# 7_power_prot_mon.net
KiCad netlist of a schematic drawn in Altium Designer
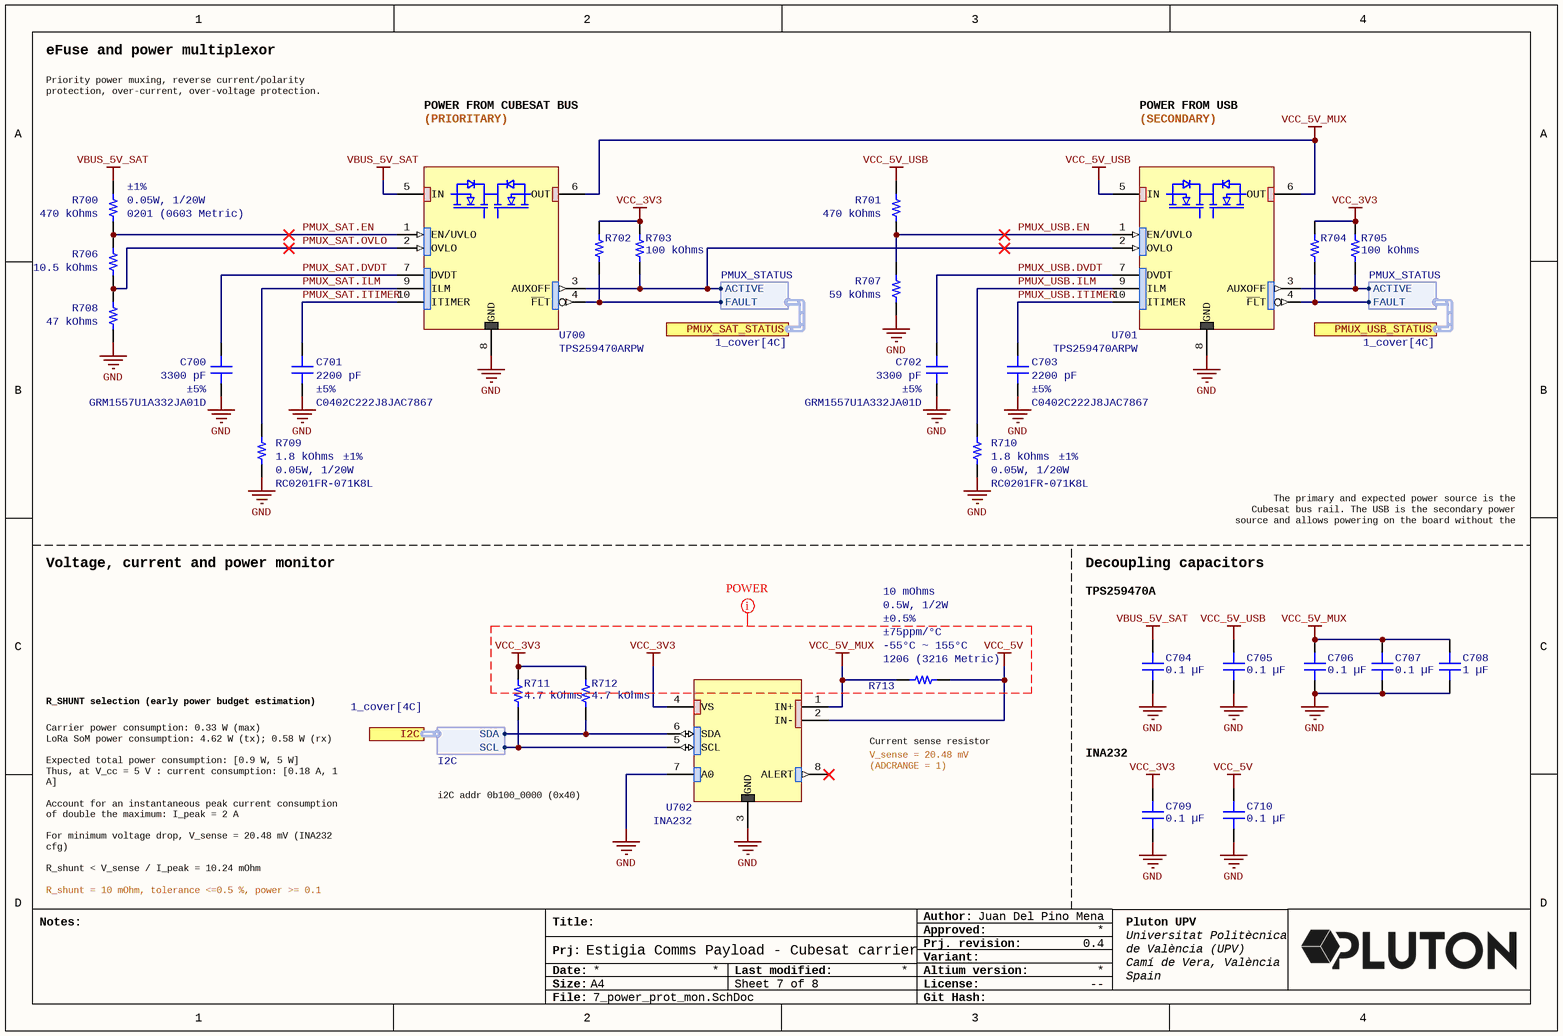
[diagram p0: 7_power_prot_mon.SchDoc]

(export (version "E")
  (design (tool "Eeschema 10.0.6"))
  (components
    (comp (ref "C700")
      (value "3300 pF")
      (footprint "CAP 0402_1005")
      (description "CAP CER 3300PF 10V U2J 0402")
      (fields
        (field (name "PART NUMBER") "GRM1557U1A332JA01D")
        (field (name "MANUFACTURER") "Murata Electronics")
        (field (name "TOLERANCE") "±5%")
      )
      (libsource (lib "Celestial Altium Library - altium_library") (part "Capacitor"))
    )
    (comp (ref "C701")
      (value "2200 pF")
      (footprint "CAP 0402_1005")
      (description "CAP CER 2200PF 10V U2J 0402")
      (fields
        (field (name "PART NUMBER") "C0402C222J8JAC7867")
        (field (name "MANUFACTURER") "KEMET")
        (field (name "TOLERANCE") "±5%")
      )
      (libsource (lib "Celestial Altium Library - altium_library") (part "Capacitor"))
    )
    (comp (ref "C702")
      (value "3300 pF")
      (footprint "CAP 0402_1005")
      (description "CAP CER 3300PF 10V U2J 0402")
      (fields
        (field (name "PART NUMBER") "GRM1557U1A332JA01D")
        (field (name "MANUFACTURER") "Murata Electronics")
        (field (name "TOLERANCE") "±5%")
      )
      (libsource (lib "Celestial Altium Library - altium_library") (part "Capacitor"))
    )
    (comp (ref "C703")
      (value "2200 pF")
      (footprint "CAP 0402_1005")
      (description "CAP CER 2200PF 10V U2J 0402")
      (fields
        (field (name "PART NUMBER") "C0402C222J8JAC7867")
        (field (name "MANUFACTURER") "KEMET")
        (field (name "TOLERANCE") "±5%")
      )
      (libsource (lib "Celestial Altium Library - altium_library") (part "Capacitor"))
    )
    (comp (ref "C704")
      (value "0.1 µF")
      (footprint "CAP 0402_1005")
      (description "CAP CER 0402 0.1UF 16V X7R 10%")
      (fields (field (name "PART NUMBER") "C0402C104K4RECAUTO") (field (name "MANUFACTURER") "KEMET"))
      (libsource (lib "Celestial Altium Library - altium_library") (part "Capacitor"))
    )
    (comp (ref "C705")
      (value "0.1 µF")
      (footprint "CAP 0402_1005")
      (description "CAP CER 0402 0.1UF 16V X7R 10%")
      (fields (field (name "PART NUMBER") "C0402C104K4RECAUTO") (field (name "MANUFACTURER") "KEMET"))
      (libsource (lib "Celestial Altium Library - altium_library") (part "Capacitor"))
    )
    (comp (ref "C706")
      (value "0.1 µF")
      (footprint "CAP 0402_1005")
      (description "CAP CER 0402 0.1UF 16V X7R 10%")
      (fields (field (name "PART NUMBER") "C0402C104K4RECAUTO") (field (name "MANUFACTURER") "KEMET"))
      (libsource (lib "Celestial Altium Library - altium_library") (part "Capacitor"))
    )
    (comp (ref "C707")
      (value "0.1 µF")
      (footprint "CAP 0402_1005")
      (description "CAP CER 0402 0.1UF 16V X7R 10%")
      (fields (field (name "PART NUMBER") "C0402C104K4RECAUTO") (field (name "MANUFACTURER") "KEMET"))
      (libsource (lib "Celestial Altium Library - altium_library") (part "Capacitor"))
    )
    (comp (ref "C708")
      (value "1 µF")
      (footprint "CAP 0402_1005")
      (description "CAP CER 1UF 10V X7S 0402")
      (fields
        (field (name "PART NUMBER") "GRT155C71A105KE13D")
        (field (name "MANUFACTURER") "Murata Electronics")
      )
      (libsource (lib "Celestial Altium Library - altium_library") (part "Capacitor"))
    )
    (comp (ref "C709")
      (value "0.1 µF")
      (footprint "CAP 0402_1005")
      (description "CAP CER 0402 0.1UF 16V X7R 10%")
      (fields (field (name "PART NUMBER") "C0402C104K4RECAUTO") (field (name "MANUFACTURER") "KEMET"))
      (libsource (lib "Celestial Altium Library - altium_library") (part "Capacitor"))
    )
    (comp (ref "C710")
      (value "0.1 µF")
      (footprint "CAP 0402_1005")
      (description "CAP CER 0402 0.1UF 16V X7R 10%")
      (fields (field (name "PART NUMBER") "C0402C104K4RECAUTO") (field (name "MANUFACTURER") "KEMET"))
      (libsource (lib "Celestial Altium Library - altium_library") (part "Capacitor"))
    )
    (comp (ref "R700")
      (value "470 kOhms")
      (footprint "RES 0201_0603")
      (description "RES 470K OHM 1% 1/20W 0201")
      (fields (field (name "PART NUMBER") "RC0201FR-13470KL") (field (name "MANUFACTURER") "Yageo"))
      (libsource (lib "Celestial Altium Library - altium_library") (part "Resistor"))
    )
    (comp (ref "R701")
      (value "470 kOhms")
      (footprint "RES 0201_0603")
      (description "RES 470K OHM 1% 1/20W 0201")
      (fields (field (name "PART NUMBER") "RC0201FR-13470KL") (field (name "MANUFACTURER") "Yageo"))
      (libsource (lib "Celestial Altium Library - altium_library") (part "Resistor"))
    )
    (comp (ref "R702")
      (value "100 kOhms")
      (footprint "RES 0201_0603")
      (description "RES 100K OHM 1% 1/20W 0201")
      (fields (field (name "PART NUMBER") "RC0201FR-13100KL") (field (name "MANUFACTURER") "Yageo"))
      (libsource (lib "Celestial Altium Library - altium_library") (part "Resistor"))
    )
    (comp (ref "R703")
      (value "100 kOhms")
      (footprint "RES 0201_0603")
      (description "RES 100K OHM 1% 1/20W 0201")
      (fields (field (name "PART NUMBER") "RC0201FR-13100KL") (field (name "MANUFACTURER") "Yageo"))
      (libsource (lib "Celestial Altium Library - altium_library") (part "Resistor"))
    )
    (comp (ref "R704")
      (value "100 kOhms")
      (footprint "RES 0201_0603")
      (description "RES 100K OHM 1% 1/20W 0201")
      (fields (field (name "PART NUMBER") "RC0201FR-13100KL") (field (name "MANUFACTURER") "Yageo"))
      (libsource (lib "Celestial Altium Library - altium_library") (part "Resistor"))
    )
    (comp (ref "R705")
      (value "100 kOhms")
      (footprint "RES 0201_0603")
      (description "RES 100K OHM 1% 1/20W 0201")
      (fields (field (name "PART NUMBER") "RC0201FR-13100KL") (field (name "MANUFACTURER") "Yageo"))
      (libsource (lib "Celestial Altium Library - altium_library") (part "Resistor"))
    )
    (comp (ref "R706")
      (value "10.5 kOhms")
      (footprint "RES 0201_0603")
      (description "RES 10.5K OHM 1% 1/20W 0201")
      (fields (field (name "PART NUMBER") "RC0201FR-0710K5L") (field (name "MANUFACTURER") "Yageo"))
      (libsource (lib "Celestial Altium Library - altium_library") (part "Resistor"))
    )
    (comp (ref "R707")
      (value "59 kOhms")
      (footprint "RES 0201_0603")
      (description "RES 59K OHM 1% 1/20W 0201")
      (fields (field (name "PART NUMBER") "RC0201FR-0759KL") (field (name "MANUFACTURER") "Yageo"))
      (libsource (lib "Celestial Altium Library - altium_library") (part "Resistor"))
    )
    (comp (ref "R708")
      (value "47 kOhms")
      (footprint "RES 0201_0603")
      (description "RES 47K OHM 1% 1/20W 0201")
      (fields
        (field (name "PART NUMBER") "RC0201FR-0747KL")
        (field (name "MANUFACTURER") "Yageo")
        (field (name "PACKAGE / CASE") "0201 (0603 Metric)")
        (field (name "POWER (WATTS)") "0.05W, 1/20W")
        (field (name "TOLERANCE") "±1%")
      )
      (libsource (lib "Celestial Altium Library - altium_library") (part "Resistor"))
    )
    (comp (ref "R709")
      (value "1.8 kOhms")
      (footprint "RES 0201_0603")
      (description "RES 1.8K OHM 1% 1/20W 0201")
      (fields
        (field (name "PART NUMBER") "RC0201FR-071K8L")
        (field (name "MANUFACTURER") "Yageo")
        (field (name "POWER (WATTS)") "0.05W, 1/20W")
        (field (name "TOLERANCE") "±1%")
      )
      (libsource (lib "Celestial Altium Library - altium_library") (part "Resistor"))
    )
    (comp (ref "R710")
      (value "1.8 kOhms")
      (footprint "RES 0201_0603")
      (description "RES 1.8K OHM 1% 1/20W 0201")
      (fields
        (field (name "PART NUMBER") "RC0201FR-071K8L")
        (field (name "MANUFACTURER") "Yageo")
        (field (name "POWER (WATTS)") "0.05W, 1/20W")
        (field (name "TOLERANCE") "±1%")
      )
      (libsource (lib "Celestial Altium Library - altium_library") (part "Resistor"))
    )
    (comp (ref "R711")
      (value "4.7 kOhms")
      (footprint "RES 0201_0603")
      (description "RES SMD 4.7K OHM 1% 1/20W 0201")
      (fields (field (name "PART NUMBER") "AC0201FR-074K7L") (field (name "MANUFACTURER") "Yageo"))
      (libsource (lib "Celestial Altium Library - altium_library") (part "Resistor"))
    )
    (comp (ref "R712")
      (value "4.7 kOhms")
      (footprint "RES 0201_0603")
      (description "RES SMD 4.7K OHM 1% 1/20W 0201")
      (fields (field (name "PART NUMBER") "AC0201FR-074K7L") (field (name "MANUFACTURER") "Yageo"))
      (libsource (lib "Celestial Altium Library - altium_library") (part "Resistor"))
    )
    (comp (ref "R713")
      (value "10 mOhms")
      (footprint "STACKPOLE CSR1206")
      (description "0.01 OHM 1206 0.5% 0.50W")
      (fields
        (field (name "PART NUMBER") "L4T12FR010DER")
        (field (name "PACKAGE / CASE") "1206 (3216 Metric)")
        (field (name "MANUFACTURER") "Ohmite")
        (field (name "OPERATING TEMPERATURE") "-55°C ~ 155°C")
        (field (name "POWER (WATTS)") "0.5W, 1/2W")
        (field (name "RESISTANCE") "10 mOhms")
        (field (name "TEMPERATURE COEFFICIENT") "±75ppm/°C")
        (field (name "TOLERANCE") "±0.5%")
      )
      (libsource (lib "Celestial Altium Library - altium_library") (part "Resistor"))
    )
    (comp (ref "U700")
      (value "TPS259470ARPW")
      (footprint "ics:VQFN-HR-TPS25947X")
      (libsource (lib "power") (part "TPS259470ARPW"))
    )
    (comp (ref "U701")
      (value "TPS259470ARPW")
      (footprint "ics:VQFN-HR-TPS25947X")
      (libsource (lib "power") (part "TPS259470ARPW"))
    )
    (comp (ref "U702")
      (value "INA232")
      (footprint "ics:SOp-23-8")
      (description "48-V, 16-Bit, Current, Voltage, and Power Monitor With an I2C Interface")
      (libsource (lib "power") (part "INA232"))
    )
  )
  (nets
    (net (code "3") (name "/PMUX_SAT.DVDT") (class "Default")
      (node (ref "C700") (pin "2") (pinfunction "2_2") (pintype "passive"))
      (node (ref "U700") (pin "7") (pinfunction "DVDT_7") (pintype "passive"))
    )
    (net (code "4") (name "/PMUX_SAT.EN") (class "Default")
      (node (ref "R700") (pin "1") (pinfunction "1_1") (pintype "passive"))
      (node (ref "R706") (pin "2") (pinfunction "2_2") (pintype "passive"))
      (node (ref "U700") (pin "1") (pinfunction "EN/UVLO_1") (pintype "input"))
    )
    (net (code "5") (name "/PMUX_SAT.ILM") (class "Default")
      (node (ref "R709") (pin "2") (pinfunction "2_2") (pintype "passive"))
      (node (ref "U700") (pin "9") (pinfunction "ILM_9") (pintype "passive"))
    )
    (net (code "6") (name "/PMUX_SAT.ITIMER") (class "Default")
      (node (ref "C701") (pin "2") (pinfunction "2_2") (pintype "passive"))
      (node (ref "U700") (pin "10") (pinfunction "ITIMER_10") (pintype "passive"))
    )
    (net (code "7") (name "/PMUX_SAT.OVLO") (class "Default")
      (node (ref "R706") (pin "1") (pinfunction "1_1") (pintype "passive"))
      (node (ref "R708") (pin "2") (pinfunction "2_2") (pintype "passive"))
      (node (ref "U700") (pin "2") (pinfunction "OVLO_2") (pintype "input"))
    )
    (net (code "8") (name "/PMUX_USB.DVDT") (class "Default")
      (node (ref "C702") (pin "2") (pinfunction "2_2") (pintype "passive"))
      (node (ref "U701") (pin "7") (pinfunction "DVDT_7") (pintype "passive"))
    )
    (net (code "9") (name "/PMUX_USB.EN") (class "Default")
      (node (ref "R701") (pin "1") (pinfunction "1_1") (pintype "passive"))
      (node (ref "R707") (pin "2") (pinfunction "2_2") (pintype "passive"))
      (node (ref "U701") (pin "1") (pinfunction "EN/UVLO_1") (pintype "input"))
    )
    (net (code "10") (name "/PMUX_USB.ILM") (class "Default")
      (node (ref "R710") (pin "2") (pinfunction "2_2") (pintype "passive"))
      (node (ref "U701") (pin "9") (pinfunction "ILM_9") (pintype "passive"))
    )
    (net (code "11") (name "/PMUX_USB.ITIMER") (class "Default")
      (node (ref "C703") (pin "2") (pinfunction "2_2") (pintype "passive"))
      (node (ref "U701") (pin "10") (pinfunction "ITIMER_10") (pintype "passive"))
    )
    (net (code "14") (name "GND") (class "Default")
      (node (ref "C700") (pin "1") (pinfunction "1_1") (pintype "passive"))
      (node (ref "C701") (pin "1") (pinfunction "1_1") (pintype "passive"))
      (node (ref "C702") (pin "1") (pinfunction "1_1") (pintype "passive"))
      (node (ref "C703") (pin "1") (pinfunction "1_1") (pintype "passive"))
      (node (ref "C704") (pin "1") (pinfunction "1_1") (pintype "passive"))
      (node (ref "C705") (pin "1") (pinfunction "1_1") (pintype "passive"))
      (node (ref "C706") (pin "1") (pinfunction "1_1") (pintype "passive"))
      (node (ref "C707") (pin "1") (pinfunction "1_1") (pintype "passive"))
      (node (ref "C708") (pin "1") (pinfunction "1_1") (pintype "passive"))
      (node (ref "C709") (pin "1") (pinfunction "1_1") (pintype "passive"))
      (node (ref "C710") (pin "1") (pinfunction "1_1") (pintype "passive"))
      (node (ref "R707") (pin "1") (pinfunction "1_1") (pintype "passive"))
      (node (ref "R708") (pin "1") (pinfunction "1_1") (pintype "passive"))
      (node (ref "R709") (pin "1") (pinfunction "1_1") (pintype "passive"))
      (node (ref "R710") (pin "1") (pinfunction "1_1") (pintype "passive"))
      (node (ref "U700") (pin "8") (pinfunction "GND_8") (pintype "power_in"))
      (node (ref "U701") (pin "8") (pinfunction "GND_8") (pintype "power_in"))
      (node (ref "U702") (pin "3") (pinfunction "GND_3") (pintype "passive"))
      (node (ref "U702") (pin "7") (pinfunction "A0_7") (pintype "passive"))
    )
    (net (code "15") (name "Net-(U700-AUXOFF)") (class "Default")
      (node (ref "R703") (pin "2") (pinfunction "2_2") (pintype "passive"))
      (node (ref "U700") (pin "3") (pinfunction "AUXOFF_3") (pintype "output"))
      (node (ref "U701") (pin "2") (pinfunction "OVLO_2") (pintype "input"))
    )
    (net (code "16") (name "Net-(U700-~{FL}T)") (class "Default")
      (node (ref "R702") (pin "2") (pinfunction "2_2") (pintype "passive"))
      (node (ref "U700") (pin "4") (pinfunction "~{FL}T_4") (pintype "output"))
    )
    (net (code "17") (name "Net-(U701-AUXOFF)") (class "Default")
      (node (ref "R705") (pin "2") (pinfunction "2_2") (pintype "passive"))
      (node (ref "U701") (pin "3") (pinfunction "AUXOFF_3") (pintype "output"))
    )
    (net (code "18") (name "Net-(U701-~{FL}T)") (class "Default")
      (node (ref "R704") (pin "2") (pinfunction "2_2") (pintype "passive"))
      (node (ref "U701") (pin "4") (pinfunction "~{FL}T_4") (pintype "output"))
    )
    (net (code "19") (name "Net-(U702-SCL)") (class "Default")
      (node (ref "R711") (pin "1") (pinfunction "1_1") (pintype "passive"))
      (node (ref "U702") (pin "5") (pinfunction "SCL_5") (pintype "bidirectional"))
    )
    (net (code "20") (name "Net-(U702-SDA)") (class "Default")
      (node (ref "R712") (pin "1") (pinfunction "1_1") (pintype "passive"))
      (node (ref "U702") (pin "6") (pinfunction "SDA_6") (pintype "bidirectional"))
    )
    (net (code "21") (name "VBUS_5V_SAT") (class "Default")
      (node (ref "C704") (pin "2") (pinfunction "2_2") (pintype "passive"))
      (node (ref "R700") (pin "2") (pinfunction "2_2") (pintype "passive"))
      (node (ref "U700") (pin "5") (pinfunction "IN_5") (pintype "power_in"))
    )
    (net (code "22") (name "VCC_3V3") (class "Default")
      (node (ref "C709") (pin "2") (pinfunction "2_2") (pintype "passive"))
      (node (ref "R702") (pin "1") (pinfunction "1_1") (pintype "passive"))
      (node (ref "R703") (pin "1") (pinfunction "1_1") (pintype "passive"))
      (node (ref "R704") (pin "1") (pinfunction "1_1") (pintype "passive"))
      (node (ref "R705") (pin "1") (pinfunction "1_1") (pintype "passive"))
      (node (ref "R711") (pin "2") (pinfunction "2_2") (pintype "passive"))
      (node (ref "R712") (pin "2") (pinfunction "2_2") (pintype "passive"))
      (node (ref "U702") (pin "4") (pinfunction "VS_4") (pintype "power_in"))
    )
    (net (code "23") (name "VCC_5V") (class "Default")
      (node (ref "C710") (pin "2") (pinfunction "2_2") (pintype "passive"))
      (node (ref "R713") (pin "1") (pinfunction "1_1") (pintype "passive"))
      (node (ref "U702") (pin "2") (pinfunction "IN-_2") (pintype "power_in"))
    )
    (net (code "24") (name "VCC_5V_MUX") (class "Default")
      (node (ref "C706") (pin "2") (pinfunction "2_2") (pintype "passive"))
      (node (ref "C707") (pin "2") (pinfunction "2_2") (pintype "passive"))
      (node (ref "C708") (pin "2") (pinfunction "2_2") (pintype "passive"))
      (node (ref "R713") (pin "2") (pinfunction "2_2") (pintype "passive"))
      (node (ref "U700") (pin "6") (pinfunction "OUT_6") (pintype "power_in"))
      (node (ref "U701") (pin "6") (pinfunction "OUT_6") (pintype "power_in"))
      (node (ref "U702") (pin "1") (pinfunction "IN+_1") (pintype "power_in"))
    )
    (net (code "25") (name "VCC_5V_USB") (class "Default")
      (node (ref "C705") (pin "2") (pinfunction "2_2") (pintype "passive"))
      (node (ref "R701") (pin "2") (pinfunction "2_2") (pintype "passive"))
      (node (ref "U701") (pin "5") (pinfunction "IN_5") (pintype "power_in"))
    )
    (net (code "26") (name "unconnected-(U702-ALERT-Pad8)") (class "Default")
      (node (ref "U702") (pin "8") (pinfunction "ALERT_8") (pintype "output+no_connect"))
    )
  )
)
